# EYIC_AD11.net
KiCad netlist of a schematic drawn in EAGLE
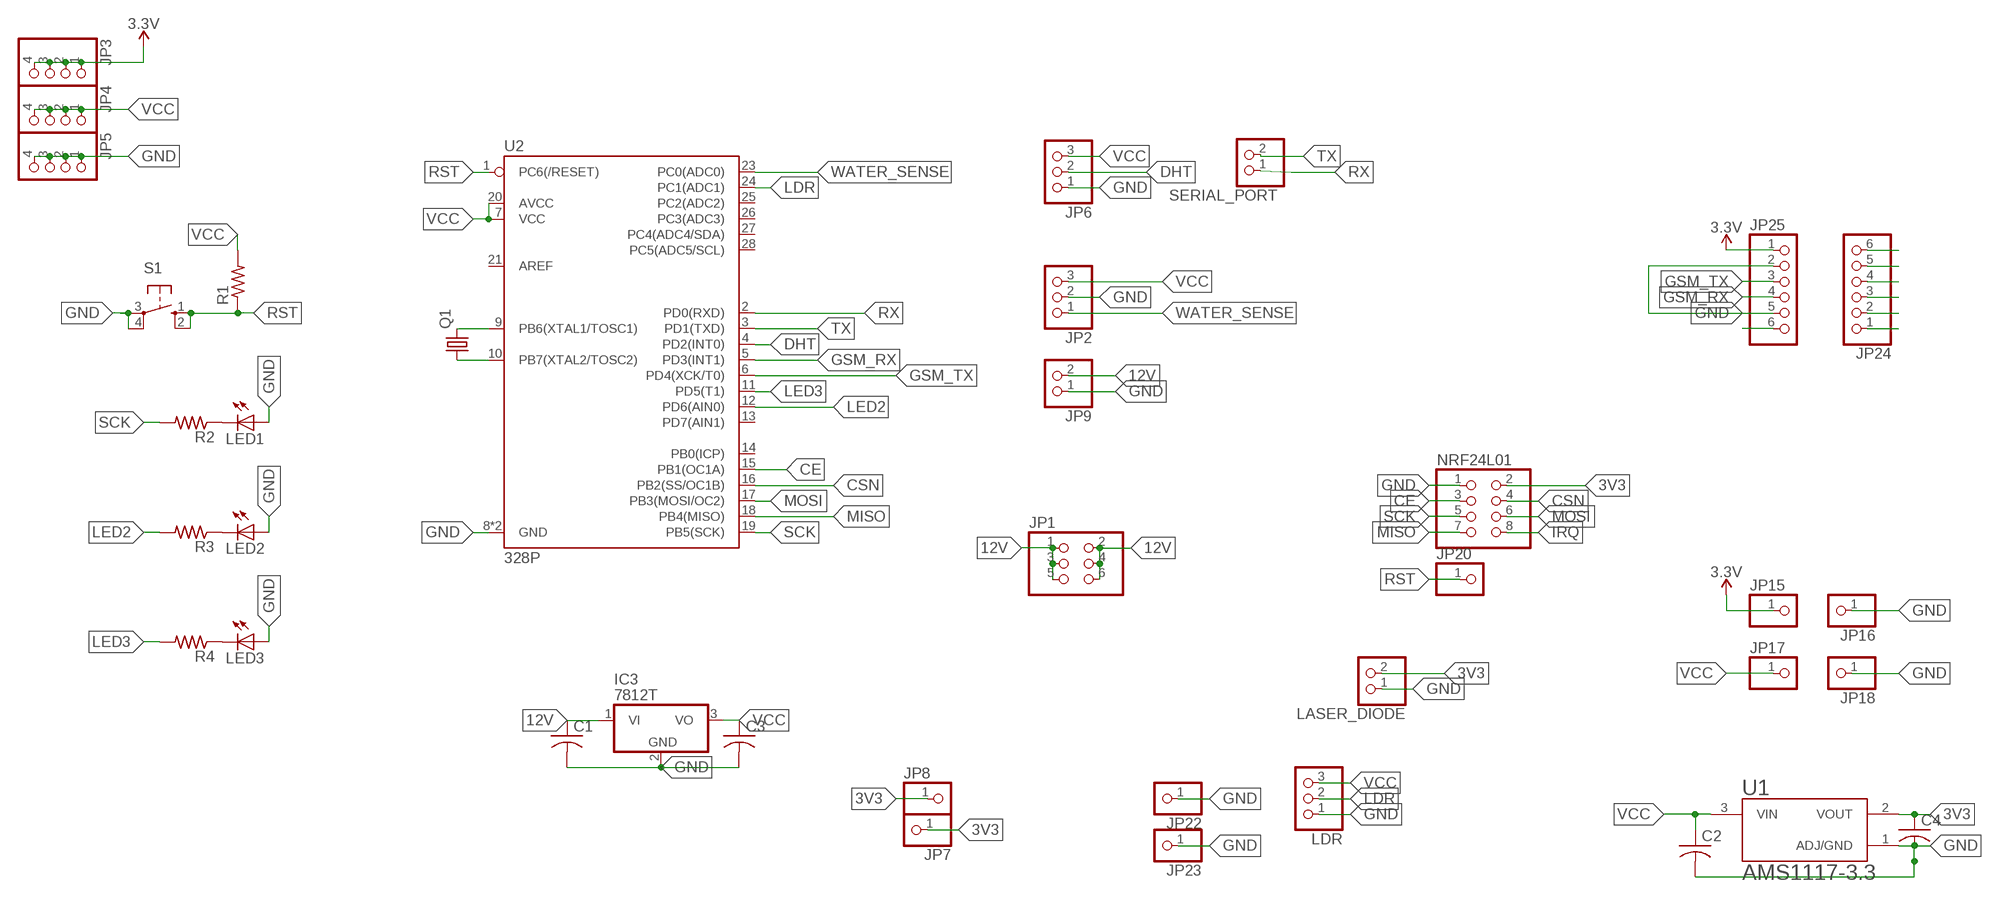
[diagram p0: schematic, sheet 1]

(export (version "E")
  (design (tool "Eeschema 10.0.6"))
  (components
    (comp (ref "C1")
      (value "C-US050-035X075")
      (footprint "eagle-import:C050-035X075")
      (libsource (lib "eagle-import") (part "C-US050-035X075"))
    )
    (comp (ref "C2")
      (value "C-US025-060X050")
      (footprint "eagle-import:C025-060X050")
      (libsource (lib "eagle-import") (part "C-US025-060X050"))
    )
    (comp (ref "C3")
      (value "C-US050-035X075")
      (footprint "eagle-import:C050-035X075")
      (libsource (lib "eagle-import") (part "C-US050-035X075"))
    )
    (comp (ref "C4")
      (value "C-US025-060X050")
      (footprint "eagle-import:C025-060X050")
      (libsource (lib "eagle-import") (part "C-US025-060X050"))
    )
    (comp (ref "IC3")
      (value "7812T")
      (footprint "eagle-import:TO220H")
      (libsource (lib "eagle-import") (part "78T12"))
    )
    (comp (ref "JP1")
      (value "PINHD-2X3")
      (footprint "eagle-import:2X03")
      (libsource (lib "eagle-import") (part "PINHD-2X3"))
    )
    (comp (ref "JP2")
      (value "PINHD-1X3")
      (footprint "eagle-import:1X03")
      (libsource (lib "eagle-import") (part "PINHD-1X3"))
    )
    (comp (ref "JP3")
      (value "PINHD-1X4")
      (footprint "eagle-import:1X04")
      (libsource (lib "eagle-import") (part "PINHD-1X4"))
    )
    (comp (ref "JP4")
      (value "PINHD-1X4")
      (footprint "eagle-import:1X04")
      (libsource (lib "eagle-import") (part "PINHD-1X4"))
    )
    (comp (ref "JP5")
      (value "PINHD-1X4")
      (footprint "eagle-import:1X04")
      (libsource (lib "eagle-import") (part "PINHD-1X4"))
    )
    (comp (ref "JP6")
      (value "PINHD-1X3")
      (footprint "eagle-import:1X03")
      (libsource (lib "eagle-import") (part "PINHD-1X3"))
    )
    (comp (ref "JP7")
      (value "PINHD-1X1")
      (footprint "eagle-import:1X01")
      (libsource (lib "eagle-import") (part "PINHD-1X1"))
    )
    (comp (ref "JP8")
      (value "PINHD-1X1")
      (footprint "eagle-import:1X01")
      (libsource (lib "eagle-import") (part "PINHD-1X1"))
    )
    (comp (ref "JP9")
      (value "PINHD-1X2")
      (footprint "eagle-import:1X02")
      (libsource (lib "eagle-import") (part "PINHD-1X2"))
    )
    (comp (ref "JP15")
      (value "PINHD-1X1")
      (footprint "eagle-import:1X01")
      (libsource (lib "eagle-import") (part "PINHD-1X1"))
    )
    (comp (ref "JP16")
      (value "PINHD-1X1")
      (footprint "eagle-import:1X01")
      (libsource (lib "eagle-import") (part "PINHD-1X1"))
    )
    (comp (ref "JP17")
      (value "PINHD-1X1")
      (footprint "eagle-import:1X01")
      (libsource (lib "eagle-import") (part "PINHD-1X1"))
    )
    (comp (ref "JP18")
      (value "PINHD-1X1")
      (footprint "eagle-import:1X01")
      (libsource (lib "eagle-import") (part "PINHD-1X1"))
    )
    (comp (ref "JP20")
      (value "PINHD-1X1")
      (footprint "eagle-import:1X01")
      (libsource (lib "eagle-import") (part "PINHD-1X1"))
    )
    (comp (ref "JP22")
      (value "PINHD-1X1")
      (footprint "eagle-import:1X01")
      (libsource (lib "eagle-import") (part "PINHD-1X1"))
    )
    (comp (ref "JP23")
      (value "PINHD-1X1")
      (footprint "eagle-import:1X01")
      (libsource (lib "eagle-import") (part "PINHD-1X1"))
    )
    (comp (ref "JP24")
      (value "PINHD-1X6")
      (footprint "eagle-import:1X06")
      (fields (field (name "SPICEPREFIX") "X"))
      (libsource (lib "eagle-import") (part "PINHD-1X6"))
    )
    (comp (ref "JP25")
      (value "PINHD-1X6")
      (footprint "eagle-import:1X06")
      (fields (field (name "SPICEPREFIX") "X"))
      (libsource (lib "eagle-import") (part "PINHD-1X6"))
    )
    (comp (ref "LASER_DIODE")
      (value "PINHD-1X2")
      (footprint "eagle-import:1X02")
      (libsource (lib "eagle-import") (part "PINHD-1X2"))
    )
    (comp (ref "LDR")
      (value "PINHD-1X3")
      (footprint "eagle-import:1X03")
      (libsource (lib "eagle-import") (part "PINHD-1X3"))
    )
    (comp (ref "LED1")
      (value "LED5MM")
      (footprint "eagle-import:LED5MM")
      (libsource (lib "eagle-import") (part "LED5MM"))
    )
    (comp (ref "LED2")
      (value "LED5MM")
      (footprint "eagle-import:LED5MM")
      (libsource (lib "eagle-import") (part "LED5MM"))
    )
    (comp (ref "LED3")
      (value "LED5MM")
      (footprint "eagle-import:LED5MM")
      (libsource (lib "eagle-import") (part "LED5MM"))
    )
    (comp (ref "NRF24L01")
      (value "PINHD-2X4")
      (footprint "eagle-import:2X04")
      (libsource (lib "eagle-import") (part "PINHD-2X4"))
    )
    (comp (ref "Q1")
      (value "CRYSTALHC49S")
      (footprint "eagle-import:HC49_S")
      (libsource (lib "eagle-import") (part "CRYSTALHC49S"))
    )
    (comp (ref "R1")
      (value "R-US_0207/7")
      (footprint "eagle-import:0207_7")
      (libsource (lib "eagle-import") (part "R-US_0207/7"))
    )
    (comp (ref "R2")
      (value "R-US_0207/7")
      (footprint "eagle-import:0207_7")
      (libsource (lib "eagle-import") (part "R-US_0207/7"))
    )
    (comp (ref "R3")
      (value "R-US_0207/7")
      (footprint "eagle-import:0207_7")
      (libsource (lib "eagle-import") (part "R-US_0207/7"))
    )
    (comp (ref "R4")
      (value "R-US_0207/7")
      (footprint "eagle-import:0207_7")
      (libsource (lib "eagle-import") (part "R-US_0207/7"))
    )
    (comp (ref "S1")
      (value "10-XX")
      (footprint "eagle-import:B3F-10XX")
      (fields (field (name "MPN") "B3F-1000"))
      (libsource (lib "eagle-import") (part "10-XX"))
    )
    (comp (ref "SERIAL_PORT")
      (value "PINHD-1X2")
      (footprint "eagle-import:1X02")
      (libsource (lib "eagle-import") (part "PINHD-1X2"))
    )
    (comp (ref "U1")
      (value "AMS1117-3.3")
      (footprint "eagle-import:SOT229P700X180-4N")
      (fields (field (name "MF") "Advanced Monolithic Systems"))
      (libsource (lib "eagle-import") (part "AMS1117-3.3"))
    )
    (comp (ref "U2")
      (value "328P")
      (footprint "eagle-import:DIP28")
      (libsource (lib "eagle-import") (part "ATMEGA328P_PDIP"))
    )
  )
  (nets
    (net (code "1") (name "3.3V") (class "Default")
      (node (ref "JP15") (pin "1") (pinfunction "1_1") (pintype "passive"))
      (node (ref "JP25") (pin "1") (pinfunction "1_1") (pintype "passive"))
      (node (ref "JP3") (pin "1") (pinfunction "1_1") (pintype "passive"))
      (node (ref "JP3") (pin "2") (pinfunction "2_2") (pintype "passive"))
      (node (ref "JP3") (pin "3") (pinfunction "3_3") (pintype "passive"))
      (node (ref "JP3") (pin "4") (pinfunction "4_4") (pintype "passive"))
    )
    (net (code "2") (name "3V3") (class "Default")
      (node (ref "C4") (pin "1") (pinfunction "1_1") (pintype "passive"))
      (node (ref "JP7") (pin "1") (pinfunction "1_1") (pintype "passive"))
      (node (ref "JP8") (pin "1") (pinfunction "1_1") (pintype "passive"))
      (node (ref "LASER_DIODE") (pin "2") (pinfunction "2_2") (pintype "passive"))
      (node (ref "NRF24L01") (pin "2") (pinfunction "2_2") (pintype "passive"))
      (node (ref "U1") (pin "2") (pinfunction "VOUT_2") (pintype "output"))
    )
    (net (code "3") (name "12V") (class "Default")
      (node (ref "C1") (pin "1") (pinfunction "1_1") (pintype "passive"))
      (node (ref "IC3") (pin "1") (pinfunction "VI_1") (pintype "input"))
      (node (ref "JP1") (pin "1") (pinfunction "1_1") (pintype "passive"))
      (node (ref "JP1") (pin "2") (pinfunction "2_2") (pintype "passive"))
      (node (ref "JP1") (pin "3") (pinfunction "3_3") (pintype "passive"))
      (node (ref "JP1") (pin "4") (pinfunction "4_4") (pintype "passive"))
      (node (ref "JP1") (pin "5") (pinfunction "5_5") (pintype "passive"))
      (node (ref "JP1") (pin "6") (pinfunction "6_6") (pintype "passive"))
      (node (ref "JP9") (pin "2") (pinfunction "2_2") (pintype "passive"))
    )
    (net (code "4") (name "CE") (class "Default")
      (node (ref "NRF24L01") (pin "3") (pinfunction "3_3") (pintype "passive"))
      (node (ref "U2") (pin "15") (pinfunction "PB1(OC1A)_15") (pintype "bidirectional"))
    )
    (net (code "5") (name "CSN") (class "Default")
      (node (ref "NRF24L01") (pin "4") (pinfunction "4_4") (pintype "passive"))
      (node (ref "U2") (pin "16") (pinfunction "PB2(SS/OC1B)_16") (pintype "bidirectional"))
    )
    (net (code "6") (name "DHT") (class "Default")
      (node (ref "JP6") (pin "2") (pinfunction "2_2") (pintype "passive"))
      (node (ref "U2") (pin "4") (pinfunction "PD2(INT0)_4") (pintype "bidirectional"))
    )
    (net (code "7") (name "GND") (class "Default")
      (node (ref "C1") (pin "2") (pinfunction "2_2") (pintype "passive"))
      (node (ref "C2") (pin "2") (pinfunction "2_2") (pintype "passive"))
      (node (ref "C3") (pin "2") (pinfunction "2_2") (pintype "passive"))
      (node (ref "C4") (pin "2") (pinfunction "2_2") (pintype "passive"))
      (node (ref "IC3") (pin "2") (pinfunction "GND_2") (pintype "passive"))
      (node (ref "JP16") (pin "1") (pinfunction "1_1") (pintype "passive"))
      (node (ref "JP18") (pin "1") (pinfunction "1_1") (pintype "passive"))
      (node (ref "JP2") (pin "2") (pinfunction "2_2") (pintype "passive"))
      (node (ref "JP22") (pin "1") (pinfunction "1_1") (pintype "passive"))
      (node (ref "JP23") (pin "1") (pinfunction "1_1") (pintype "passive"))
      (node (ref "JP25") (pin "2") (pinfunction "2_2") (pintype "passive"))
      (node (ref "JP25") (pin "5") (pinfunction "5_5") (pintype "passive"))
      (node (ref "JP5") (pin "1") (pinfunction "1_1") (pintype "passive"))
      (node (ref "JP5") (pin "2") (pinfunction "2_2") (pintype "passive"))
      (node (ref "JP5") (pin "3") (pinfunction "3_3") (pintype "passive"))
      (node (ref "JP5") (pin "4") (pinfunction "4_4") (pintype "passive"))
      (node (ref "JP6") (pin "1") (pinfunction "1_1") (pintype "passive"))
      (node (ref "JP9") (pin "1") (pinfunction "1_1") (pintype "passive"))
      (node (ref "LASER_DIODE") (pin "1") (pinfunction "1_1") (pintype "passive"))
      (node (ref "LDR") (pin "1") (pinfunction "1_1") (pintype "passive"))
      (node (ref "LED1") (pin "A") (pinfunction "A_A") (pintype "passive"))
      (node (ref "LED2") (pin "A") (pinfunction "A_A") (pintype "passive"))
      (node (ref "LED3") (pin "A") (pinfunction "A_A") (pintype "passive"))
      (node (ref "NRF24L01") (pin "1") (pinfunction "1_1") (pintype "passive"))
      (node (ref "S1") (pin "3") (pinfunction "P_3") (pintype "passive"))
      (node (ref "S1") (pin "4") (pinfunction "P1_4") (pintype "passive"))
      (node (ref "U1") (pin "1") (pinfunction "ADJ/GND_1") (pintype "power_in"))
      (node (ref "U2") (pin "22") (pinfunction "GND_22") (pintype "bidirectional"))
      (node (ref "U2") (pin "8") (pinfunction "GND_8") (pintype "bidirectional"))
    )
    (net (code "8") (name "GSM_RX") (class "Default")
      (node (ref "JP25") (pin "4") (pinfunction "4_4") (pintype "passive"))
      (node (ref "U2") (pin "5") (pinfunction "PD3(INT1)_5") (pintype "bidirectional"))
    )
    (net (code "9") (name "GSM_TX") (class "Default")
      (node (ref "JP25") (pin "3") (pinfunction "3_3") (pintype "passive"))
      (node (ref "U2") (pin "6") (pinfunction "PD4(XCK/T0)_6") (pintype "bidirectional"))
    )
    (net (code "10") (name "IRQ") (class "Default")
      (node (ref "NRF24L01") (pin "8") (pinfunction "8_8") (pintype "passive"))
    )
    (net (code "11") (name "LDR") (class "Default")
      (node (ref "LDR") (pin "2") (pinfunction "2_2") (pintype "passive"))
      (node (ref "U2") (pin "24") (pinfunction "PC1(ADC1)_24") (pintype "bidirectional"))
    )
    (net (code "12") (name "LED2") (class "Default")
      (node (ref "R3") (pin "2") (pinfunction "2_2") (pintype "passive"))
      (node (ref "U2") (pin "12") (pinfunction "PD6(AIN0)_12") (pintype "bidirectional"))
    )
    (net (code "13") (name "LED3") (class "Default")
      (node (ref "R4") (pin "2") (pinfunction "2_2") (pintype "passive"))
      (node (ref "U2") (pin "11") (pinfunction "PD5(T1)_11") (pintype "bidirectional"))
    )
    (net (code "14") (name "MISO") (class "Default")
      (node (ref "NRF24L01") (pin "7") (pinfunction "7_7") (pintype "passive"))
      (node (ref "U2") (pin "18") (pinfunction "PB4(MISO)_18") (pintype "bidirectional"))
    )
    (net (code "15") (name "MOSI") (class "Default")
      (node (ref "NRF24L01") (pin "6") (pinfunction "6_6") (pintype "passive"))
      (node (ref "U2") (pin "17") (pinfunction "PB3(MOSI/OC2)_17") (pintype "bidirectional"))
    )
    (net (code "16") (name "Net-(LED1-C)") (class "Default")
      (node (ref "LED1") (pin "K") (pinfunction "C_K") (pintype "passive"))
      (node (ref "R2") (pin "1") (pinfunction "1_1") (pintype "passive"))
    )
    (net (code "17") (name "Net-(LED2-C)") (class "Default")
      (node (ref "LED2") (pin "K") (pinfunction "C_K") (pintype "passive"))
      (node (ref "R3") (pin "1") (pinfunction "1_1") (pintype "passive"))
    )
    (net (code "18") (name "Net-(LED3-C)") (class "Default")
      (node (ref "LED3") (pin "K") (pinfunction "C_K") (pintype "passive"))
      (node (ref "R4") (pin "1") (pinfunction "1_1") (pintype "passive"))
    )
    (net (code "19") (name "Net-(U2-PB6(XTAL1{slash}TOSC1))") (class "Default")
      (node (ref "Q1") (pin "2") (pinfunction "2_2") (pintype "passive"))
      (node (ref "U2") (pin "9") (pinfunction "PB6(XTAL1/TOSC1)_9") (pintype "bidirectional"))
    )
    (net (code "20") (name "Net-(U2-PB7(XTAL2{slash}TOSC2))") (class "Default")
      (node (ref "Q1") (pin "1") (pinfunction "1_1") (pintype "passive"))
      (node (ref "U2") (pin "10") (pinfunction "PB7(XTAL2/TOSC2)_10") (pintype "bidirectional"))
    )
    (net (code "21") (name "RST") (class "Default")
      (node (ref "JP20") (pin "1") (pinfunction "1_1") (pintype "passive"))
      (node (ref "R1") (pin "1") (pinfunction "1_1") (pintype "passive"))
      (node (ref "S1") (pin "1") (pinfunction "S_1") (pintype "passive"))
      (node (ref "S1") (pin "2") (pinfunction "S1_2") (pintype "passive"))
      (node (ref "U2") (pin "1") (pinfunction "PC6(/RESET)_1") (pintype "bidirectional"))
    )
    (net (code "22") (name "RX") (class "Default")
      (node (ref "SERIAL_PORT") (pin "1") (pinfunction "1_1") (pintype "passive"))
      (node (ref "U2") (pin "2") (pinfunction "PD0(RXD)_2") (pintype "bidirectional"))
    )
    (net (code "23") (name "SCK") (class "Default")
      (node (ref "NRF24L01") (pin "5") (pinfunction "5_5") (pintype "passive"))
      (node (ref "R2") (pin "2") (pinfunction "2_2") (pintype "passive"))
      (node (ref "U2") (pin "19") (pinfunction "PB5(SCK)_19") (pintype "bidirectional"))
    )
    (net (code "24") (name "TX") (class "Default")
      (node (ref "SERIAL_PORT") (pin "2") (pinfunction "2_2") (pintype "passive"))
      (node (ref "U2") (pin "3") (pinfunction "PD1(TXD)_3") (pintype "bidirectional"))
    )
    (net (code "25") (name "VCC") (class "Default")
      (node (ref "C2") (pin "1") (pinfunction "1_1") (pintype "passive"))
      (node (ref "C3") (pin "1") (pinfunction "1_1") (pintype "passive"))
      (node (ref "IC3") (pin "3") (pinfunction "VO_3") (pintype "passive"))
      (node (ref "JP17") (pin "1") (pinfunction "1_1") (pintype "passive"))
      (node (ref "JP2") (pin "3") (pinfunction "3_3") (pintype "passive"))
      (node (ref "JP4") (pin "1") (pinfunction "1_1") (pintype "passive"))
      (node (ref "JP4") (pin "2") (pinfunction "2_2") (pintype "passive"))
      (node (ref "JP4") (pin "3") (pinfunction "3_3") (pintype "passive"))
      (node (ref "JP4") (pin "4") (pinfunction "4_4") (pintype "passive"))
      (node (ref "JP6") (pin "3") (pinfunction "3_3") (pintype "passive"))
      (node (ref "LDR") (pin "3") (pinfunction "3_3") (pintype "passive"))
      (node (ref "R1") (pin "2") (pinfunction "2_2") (pintype "passive"))
      (node (ref "U1") (pin "3") (pinfunction "VIN_3") (pintype "input"))
      (node (ref "U2") (pin "20") (pinfunction "AVCC_20") (pintype "bidirectional"))
      (node (ref "U2") (pin "7") (pinfunction "VCC_7") (pintype "bidirectional"))
    )
    (net (code "26") (name "WATER_SENSE") (class "Default")
      (node (ref "JP2") (pin "1") (pinfunction "1_1") (pintype "passive"))
      (node (ref "U2") (pin "23") (pinfunction "PC0(ADC0)_23") (pintype "bidirectional"))
    )
    (net (code "27") (name "unconnected-(JP24-Pad1)") (class "Default")
      (node (ref "JP24") (pin "1") (pinfunction "1_1") (pintype "passive"))
    )
    (net (code "28") (name "unconnected-(JP24-Pad2)") (class "Default")
      (node (ref "JP24") (pin "2") (pinfunction "2_2") (pintype "passive"))
    )
    (net (code "29") (name "unconnected-(JP24-Pad3)") (class "Default")
      (node (ref "JP24") (pin "3") (pinfunction "3_3") (pintype "passive"))
    )
    (net (code "30") (name "unconnected-(JP24-Pad4)") (class "Default")
      (node (ref "JP24") (pin "4") (pinfunction "4_4") (pintype "passive"))
    )
    (net (code "31") (name "unconnected-(JP24-Pad5)") (class "Default")
      (node (ref "JP24") (pin "5") (pinfunction "5_5") (pintype "passive"))
    )
    (net (code "32") (name "unconnected-(JP24-Pad6)") (class "Default")
      (node (ref "JP24") (pin "6") (pinfunction "6_6") (pintype "passive"))
    )
    (net (code "33") (name "unconnected-(JP25-Pad6)") (class "Default")
      (node (ref "JP25") (pin "6") (pinfunction "6_6") (pintype "passive"))
    )
    (net (code "34") (name "unconnected-(U2-AREF-Pad21)") (class "Default")
      (node (ref "U2") (pin "21") (pinfunction "AREF_21") (pintype "bidirectional"))
    )
    (net (code "35") (name "unconnected-(U2-PB0(ICP)-Pad14)") (class "Default")
      (node (ref "U2") (pin "14") (pinfunction "PB0(ICP)_14") (pintype "bidirectional"))
    )
    (net (code "36") (name "unconnected-(U2-PC2(ADC2)-Pad25)") (class "Default")
      (node (ref "U2") (pin "25") (pinfunction "PC2(ADC2)_25") (pintype "bidirectional"))
    )
    (net (code "37") (name "unconnected-(U2-PC3(ADC3)-Pad26)") (class "Default")
      (node (ref "U2") (pin "26") (pinfunction "PC3(ADC3)_26") (pintype "bidirectional"))
    )
    (net (code "38") (name "unconnected-(U2-PC4(ADC4{slash}SDA)-Pad27)") (class "Default")
      (node (ref "U2") (pin "27") (pinfunction "PC4(ADC4/SDA)_27") (pintype "bidirectional"))
    )
    (net (code "39") (name "unconnected-(U2-PC5(ADC5{slash}SCL)-Pad28)") (class "Default")
      (node (ref "U2") (pin "28") (pinfunction "PC5(ADC5/SCL)_28") (pintype "bidirectional"))
    )
    (net (code "40") (name "unconnected-(U2-PD7(AIN1)-Pad13)") (class "Default")
      (node (ref "U2") (pin "13") (pinfunction "PD7(AIN1)_13") (pintype "bidirectional"))
    )
  )
)
